# Sheet1.net
KiCad netlist of a schematic drawn in Altium Designer
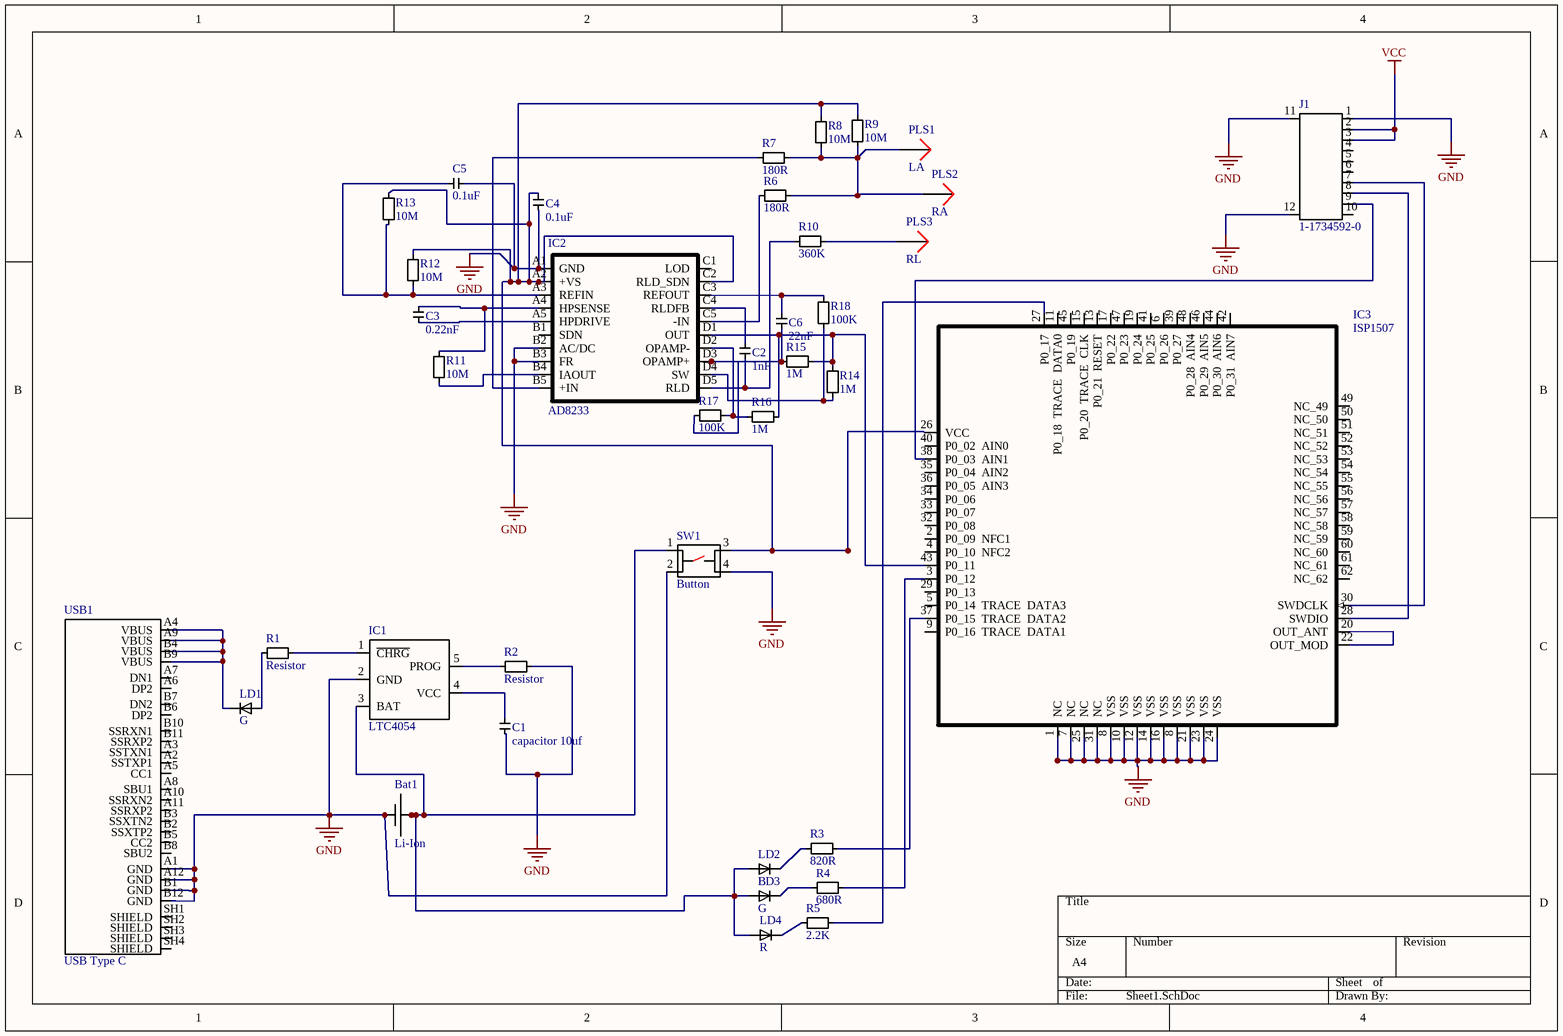
[diagram p0: Sheet1.SchDoc]

(export (version "E")
  (design (tool "Eeschema 10.0.6"))
  (components
    (comp (ref "Bat1") (value "Li-Ion") (footprint "LI-ion") (libsource (lib "Schlib1") (part "Li-Ion")))
    (comp (ref "C2") (value "1nF") (footprint "Capac") (libsource (lib "Schlib1") (part "capacitor 1uf")))
    (comp (ref "C3") (value "0.22nF") (footprint "Capac") (libsource (lib "Schlib1") (part "capacitor 1uf")))
    (comp (ref "C4") (value "0.1uF") (footprint "Capac") (libsource (lib "Schlib1") (part "capacitor 1uf")))
    (comp (ref "C5") (value "0.1uF") (footprint "Capac") (libsource (lib "Schlib1") (part "capacitor 1uf")))
    (comp (ref "C6") (value "22nF") (footprint "Capac") (libsource (lib "Schlib1") (part "capacitor 1uf")))
    (comp (ref "IC1") (value "LTC4054") (footprint "LTC4054") (libsource (lib "Schlib1") (part "LTC4054")))
    (comp (ref "IC2") (value "AD8233") (footprint "AD8233") (libsource (lib "Schlib1") (part "AD8233")))
    (comp (ref "IC3") (value "ISP1507") (footprint "ISP1507") (libsource (lib "Schlib1") (part "ISP1507")))
    (comp (ref "J1")
      (value "1-1734592-0")
      (footprint "1-1734592-0")
      (libsource (lib "Schlib1") (part "1-1734592-0"))
    )
    (comp (ref "LD1") (value "G") (footprint "LED") (libsource (lib "Schlib1") (part "led")))
    (comp (ref "LD2") (value "B") (footprint "LED") (libsource (lib "Schlib1") (part "led")))
    (comp (ref "LD3") (value "G") (footprint "LED") (libsource (lib "Schlib1") (part "led")))
    (comp (ref "LD4") (value "R") (footprint "LED") (libsource (lib "Schlib1") (part "led")))
    (comp (ref "PLS1") (value "LA") (footprint "output") (libsource (lib "Schlib1") (part "Output")))
    (comp (ref "PLS2") (value "RA") (footprint "output") (libsource (lib "Schlib1") (part "Output")))
    (comp (ref "PLS3") (value "RL") (footprint "output") (libsource (lib "Schlib1") (part "Output")))
    (comp (ref "R1")
      (value "Resistor")
      (footprint "Resistor 1")
      (libsource (lib "Schlib1") (part "Resistor"))
    )
    (comp (ref "R2")
      (value "Resistor")
      (footprint "Resistor 1")
      (libsource (lib "Schlib1") (part "Resistor"))
    )
    (comp (ref "R3") (value "820R") (footprint "Resistor 1") (libsource (lib "Schlib1") (part "Resistor")))
    (comp (ref "R4") (value "680R") (footprint "Resistor 1") (libsource (lib "Schlib1") (part "Resistor")))
    (comp (ref "R5") (value "2.2K") (footprint "Resistor 1") (libsource (lib "Schlib1") (part "Resistor")))
    (comp (ref "R6") (value "180R") (footprint "Resistor 1") (libsource (lib "Schlib1") (part "Resistor")))
    (comp (ref "R7") (value "180R") (footprint "Resistor 1") (libsource (lib "Schlib1") (part "Resistor")))
    (comp (ref "R8") (value "10M") (footprint "Resistor 1") (libsource (lib "Schlib1") (part "Resistor")))
    (comp (ref "R9") (value "10M") (footprint "Resistor 1") (libsource (lib "Schlib1") (part "Resistor")))
    (comp (ref "R10") (value "360K") (footprint "Resistor 1") (libsource (lib "Schlib1") (part "Resistor")))
    (comp (ref "R11") (value "10M") (footprint "Resistor 1") (libsource (lib "Schlib1") (part "Resistor")))
    (comp (ref "R12") (value "10M") (footprint "Resistor 1") (libsource (lib "Schlib1") (part "Resistor")))
    (comp (ref "R13") (value "10M") (footprint "Resistor 1") (libsource (lib "Schlib1") (part "Resistor")))
    (comp (ref "R14") (value "1M") (footprint "Resistor 1") (libsource (lib "Schlib1") (part "Resistor")))
    (comp (ref "R15") (value "1M") (footprint "Resistor 1") (libsource (lib "Schlib1") (part "Resistor")))
    (comp (ref "R16") (value "1M") (footprint "Resistor 1") (libsource (lib "Schlib1") (part "Resistor")))
    (comp (ref "R17") (value "100K") (footprint "Resistor 1") (libsource (lib "Schlib1") (part "Resistor")))
    (comp (ref "R18") (value "100K") (footprint "Resistor 1") (libsource (lib "Schlib1") (part "Resistor")))
    (comp (ref "SW1") (value "Button") (footprint "Button") (libsource (lib "Schlib1") (part "Button")))
    (comp (ref "USB1")
      (value "USB Type C")
      (footprint "Type C")
      (libsource (lib "Schlib1") (part "USB Type C"))
    )
    (comp (ref "С1")
      (value "capacitor 10uf")
      (footprint "CAPAC10")
      (libsource (lib "Schlib1") (part "capacitor 10uf"))
    )
  )
  (nets
    (net (code "1") (name "GND") (class "Default")
      (node (ref "Bat1") (pin "1") (pintype "passive"))
      (node (ref "Bat1") (pin "2") (pinfunction "2_2") (pintype "passive"))
      (node (ref "C4") (pin "1") (pinfunction "1_1") (pintype "passive"))
      (node (ref "C5") (pin "2") (pinfunction "2_2") (pintype "passive"))
      (node (ref "IC1") (pin "2") (pinfunction "GND_2") (pintype "power_in"))
      (node (ref "IC2") (pin "A1") (pinfunction "GND_A1") (pintype "passive"))
      (node (ref "IC2") (pin "B2") (pinfunction "AC/DC_B2") (pintype "power_in"))
      (node (ref "IC2") (pin "B3") (pinfunction "FR_B3") (pintype "power_in"))
      (node (ref "IC3") (pin "1") (pinfunction "NC_1") (pintype "power_in"))
      (node (ref "IC3") (pin "10") (pinfunction "VSS_10") (pintype "power_in"))
      (node (ref "IC3") (pin "12") (pinfunction "VSS_12") (pintype "power_in"))
      (node (ref "IC3") (pin "14") (pinfunction "VSS_14") (pintype "power_in"))
      (node (ref "IC3") (pin "16") (pinfunction "VSS_16") (pintype "power_in"))
      (node (ref "IC3") (pin "21") (pinfunction "VSS_21") (pintype "power_in"))
      (node (ref "IC3") (pin "23") (pinfunction "VSS_23") (pintype "power_in"))
      (node (ref "IC3") (pin "24") (pinfunction "VSS_24") (pintype "power_in"))
      (node (ref "IC3") (pin "25") (pinfunction "NC_25") (pintype "power_in"))
      (node (ref "IC3") (pin "31") (pinfunction "NC_31") (pintype "power_in"))
      (node (ref "IC3") (pin "7") (pinfunction "NC_7") (pintype "power_in"))
      (node (ref "IC3") (pin "8") (pinfunction "VSS_8") (pintype "power_in"))
      (node (ref "J1") (pin "1") (pinfunction "1_1") (pintype "passive"))
      (node (ref "J1") (pin "11") (pinfunction "11_11") (pintype "passive"))
      (node (ref "J1") (pin "12") (pinfunction "12_12") (pintype "passive"))
      (node (ref "R2") (pin "2") (pinfunction "2_2") (pintype "passive"))
      (node (ref "SW1") (pin "2") (pinfunction "2_2") (pintype "passive"))
      (node (ref "SW1") (pin "4") (pinfunction "4_4") (pintype "passive"))
      (node (ref "USB1") (pin "A1") (pinfunction "GND_A1") (pintype "passive"))
      (node (ref "USB1") (pin "A12") (pinfunction "GND_A12") (pintype "passive"))
      (node (ref "USB1") (pin "B1") (pinfunction "GND_B1") (pintype "passive"))
      (node (ref "USB1") (pin "B12") (pinfunction "GND_B12") (pintype "passive"))
      (node (ref "С1") (pin "1") (pinfunction "1_1") (pintype "passive"))
    )
    (net (code "2") (name "Net-(IC1-BAT)") (class "Default")
      (node (ref "Bat1") (pin "3") (pinfunction "3_3") (pintype "passive"))
      (node (ref "Bat1") (pin "4") (pinfunction "4_4") (pintype "passive"))
      (node (ref "Bat1") (pin "5") (pinfunction "5_5") (pintype "passive"))
      (node (ref "IC1") (pin "3") (pinfunction "BAT_3") (pintype "passive"))
      (node (ref "LD2") (pin "1") (pinfunction "1_1") (pintype "passive"))
      (node (ref "LD3") (pin "1") (pinfunction "1_1") (pintype "passive"))
      (node (ref "LD4") (pin "1") (pinfunction "1_1") (pintype "passive"))
      (node (ref "SW1") (pin "1") (pinfunction "1_1") (pintype "passive"))
    )
    (net (code "3") (name "Net-(IC1-PROG)") (class "Default")
      (node (ref "IC1") (pin "5") (pinfunction "PROG_5") (pintype "passive"))
      (node (ref "R2") (pin "1") (pinfunction "1_1") (pintype "passive"))
    )
    (net (code "4") (name "Net-(IC1-VCC)") (class "Default")
      (node (ref "IC1") (pin "4") (pinfunction "VCC_4") (pintype "power_in"))
      (node (ref "С1") (pin "2") (pinfunction "2_2") (pintype "passive"))
    )
    (net (code "5") (name "Net-(IC1-~{CHRG})") (class "Default")
      (node (ref "IC1") (pin "1") (pinfunction "~{CHRG}_1") (pintype "passive"))
      (node (ref "R1") (pin "2") (pinfunction "2_2") (pintype "passive"))
    )
    (net (code "6") (name "Net-(IC2-+IN)") (class "Default")
      (node (ref "IC2") (pin "B5") (pinfunction "+IN_B5") (pintype "power_in"))
      (node (ref "R7") (pin "1") (pinfunction "1_1") (pintype "passive"))
    )
    (net (code "7") (name "Net-(IC2-+VS)") (class "Default")
      (node (ref "C4") (pin "2") (pinfunction "2_2") (pintype "passive"))
      (node (ref "IC2") (pin "A2") (pinfunction "+VS_A2") (pintype "passive"))
      (node (ref "IC2") (pin "C2") (pinfunction "RLD_SDN_C2") (pintype "power_in"))
      (node (ref "IC3") (pin "26") (pinfunction "VCC_26") (pintype "power_in"))
      (node (ref "R12") (pin "2") (pinfunction "2_2") (pintype "passive"))
      (node (ref "R13") (pin "2") (pinfunction "2_2") (pintype "passive"))
      (node (ref "R8") (pin "2") (pinfunction "2_2") (pintype "passive"))
      (node (ref "R9") (pin "2") (pinfunction "2_2") (pintype "passive"))
      (node (ref "SW1") (pin "3") (pinfunction "3_3") (pintype "passive"))
    )
    (net (code "8") (name "Net-(IC2--IN)") (class "Default")
      (node (ref "IC2") (pin "C5") (pinfunction "-IN_C5") (pintype "power_in"))
      (node (ref "R6") (pin "1") (pinfunction "1_1") (pintype "passive"))
    )
    (net (code "9") (name "Net-(IC2-HPDRIVE)") (class "Default")
      (node (ref "C3") (pin "1") (pinfunction "1_1") (pintype "passive"))
      (node (ref "IC2") (pin "A5") (pinfunction "HPDRIVE_A5") (pintype "power_in"))
    )
    (net (code "10") (name "Net-(IC2-HPSENSE)") (class "Default")
      (node (ref "C3") (pin "2") (pinfunction "2_2") (pintype "passive"))
      (node (ref "IC2") (pin "A4") (pinfunction "HPSENSE_A4") (pintype "passive"))
      (node (ref "R11") (pin "2") (pinfunction "2_2") (pintype "passive"))
    )
    (net (code "11") (name "Net-(IC2-IAOUT)") (class "Default")
      (node (ref "IC2") (pin "B4") (pinfunction "IAOUT_B4") (pintype "power_in"))
      (node (ref "R11") (pin "1") (pinfunction "1_1") (pintype "passive"))
    )
    (net (code "12") (name "Net-(IC2-OPAMP+)") (class "Default")
      (node (ref "C6") (pin "1") (pinfunction "1_1") (pintype "passive"))
      (node (ref "IC2") (pin "D3") (pinfunction "OPAMP+_D3") (pintype "power_in"))
      (node (ref "R15") (pin "1") (pinfunction "1_1") (pintype "passive"))
      (node (ref "R17") (pin "1") (pinfunction "1_1") (pintype "passive"))
    )
    (net (code "13") (name "Net-(IC2-OPAMP-)") (class "Default")
      (node (ref "IC2") (pin "D2") (pinfunction "OPAMP-_D2") (pintype "power_in"))
      (node (ref "R16") (pin "1") (pinfunction "1_1") (pintype "passive"))
      (node (ref "R17") (pin "2") (pinfunction "2_2") (pintype "passive"))
    )
    (net (code "14") (name "Net-(IC2-OUT)") (class "Default")
      (node (ref "IC2") (pin "D1") (pinfunction "OUT_D1") (pintype "power_in"))
      (node (ref "IC3") (pin "43") (pinfunction "P0_11_43") (pintype "bidirectional"))
      (node (ref "R14") (pin "2") (pinfunction "2_2") (pintype "passive"))
      (node (ref "R15") (pin "2") (pinfunction "2_2") (pintype "passive"))
      (node (ref "R16") (pin "2") (pinfunction "2_2") (pintype "passive"))
    )
    (net (code "15") (name "Net-(IC2-REFIN)") (class "Default")
      (node (ref "C5") (pin "1") (pinfunction "1_1") (pintype "passive"))
      (node (ref "IC2") (pin "A3") (pinfunction "REFIN_A3") (pintype "passive"))
      (node (ref "R12") (pin "1") (pinfunction "1_1") (pintype "passive"))
      (node (ref "R13") (pin "1") (pinfunction "1_1") (pintype "passive"))
    )
    (net (code "16") (name "Net-(IC2-REFOUT)") (class "Default")
      (node (ref "C6") (pin "2") (pinfunction "2_2") (pintype "passive"))
      (node (ref "IC2") (pin "C3") (pinfunction "REFOUT_C3") (pintype "power_in"))
      (node (ref "R18") (pin "2") (pinfunction "2_2") (pintype "passive"))
    )
    (net (code "17") (name "Net-(IC2-RLD)") (class "Default")
      (node (ref "C2") (pin "2") (pinfunction "2_2") (pintype "passive"))
      (node (ref "IC2") (pin "D5") (pinfunction "RLD_D5") (pintype "power_in"))
      (node (ref "R10") (pin "1") (pinfunction "1_1") (pintype "passive"))
    )
    (net (code "18") (name "Net-(IC2-RLDFB)") (class "Default")
      (node (ref "C2") (pin "1") (pinfunction "1_1") (pintype "passive"))
      (node (ref "IC2") (pin "C4") (pinfunction "RLDFB_C4") (pintype "power_in"))
    )
    (net (code "19") (name "Net-(IC2-SW)") (class "Default")
      (node (ref "IC2") (pin "D4") (pinfunction "SW_D4") (pintype "power_in"))
      (node (ref "R14") (pin "1") (pinfunction "1_1") (pintype "passive"))
      (node (ref "R18") (pin "1") (pinfunction "1_1") (pintype "passive"))
    )
    (net (code "20") (name "Net-(IC3-OUT_ANT)") (class "Default")
      (node (ref "IC3") (pin "20") (pinfunction "OUT_ANT_20") (pintype "bidirectional"))
      (node (ref "IC3") (pin "22") (pinfunction "OUT_MOD_22") (pintype "bidirectional"))
    )
    (net (code "21") (name "Net-(IC3-P0_03__AIN1)") (class "Default")
      (node (ref "IC3") (pin "38") (pinfunction "P0_03__AIN1_38") (pintype "bidirectional"))
      (node (ref "J1") (pin "9") (pinfunction "9_9") (pintype "passive"))
    )
    (net (code "22") (name "Net-(IC3-P0_12)") (class "Default")
      (node (ref "IC3") (pin "3") (pinfunction "P0_12_3") (pintype "bidirectional"))
      (node (ref "R4") (pin "2") (pinfunction "2_2") (pintype "passive"))
    )
    (net (code "23") (name "Net-(IC3-P0_15__TRACE__DATA2)") (class "Default")
      (node (ref "IC3") (pin "37") (pinfunction "P0_15__TRACE__DATA2_37") (pintype "bidirectional"))
      (node (ref "R3") (pin "2") (pinfunction "2_2") (pintype "passive"))
    )
    (net (code "24") (name "Net-(IC3-P0_17)") (class "Default")
      (node (ref "IC3") (pin "27") (pinfunction "P0_17_27") (pintype "bidirectional"))
      (node (ref "R5") (pin "2") (pinfunction "2_2") (pintype "passive"))
    )
    (net (code "25") (name "Net-(IC3-SWDCLK)") (class "Default")
      (node (ref "IC3") (pin "30") (pinfunction "SWDCLK_30") (pintype "input"))
      (node (ref "J1") (pin "7") (pinfunction "7_7") (pintype "passive"))
    )
    (net (code "26") (name "Net-(IC3-SWDIO)") (class "Default")
      (node (ref "IC3") (pin "28") (pinfunction "SWDIO_28") (pintype "bidirectional"))
      (node (ref "J1") (pin "8") (pinfunction "8_8") (pintype "passive"))
    )
    (net (code "27") (name "Net-(LD1-Pad1)") (class "Default")
      (node (ref "LD1") (pin "1") (pinfunction "1_1") (pintype "passive"))
      (node (ref "R1") (pin "1") (pinfunction "1_1") (pintype "passive"))
    )
    (net (code "28") (name "Net-(LD1-Pad2)") (class "Default")
      (node (ref "LD1") (pin "2") (pinfunction "2_2") (pintype "passive"))
      (node (ref "USB1") (pin "A4") (pinfunction "VBUS_A4") (pintype "passive"))
      (node (ref "USB1") (pin "A9") (pinfunction "VBUS_A9") (pintype "passive"))
      (node (ref "USB1") (pin "B4") (pinfunction "VBUS_B4") (pintype "passive"))
      (node (ref "USB1") (pin "B9") (pinfunction "VBUS_B9") (pintype "passive"))
    )
    (net (code "29") (name "Net-(LD2-Pad2)") (class "Default")
      (node (ref "LD2") (pin "2") (pinfunction "2_2") (pintype "passive"))
      (node (ref "R3") (pin "1") (pinfunction "1_1") (pintype "passive"))
    )
    (net (code "30") (name "Net-(LD3-Pad2)") (class "Default")
      (node (ref "LD3") (pin "2") (pinfunction "2_2") (pintype "passive"))
      (node (ref "R4") (pin "1") (pinfunction "1_1") (pintype "passive"))
    )
    (net (code "31") (name "Net-(LD4-Pad2)") (class "Default")
      (node (ref "LD4") (pin "2") (pinfunction "2_2") (pintype "passive"))
      (node (ref "R5") (pin "1") (pinfunction "1_1") (pintype "passive"))
    )
    (net (code "32") (name "Net-(PLS1-Pad1)") (class "Default")
      (node (ref "PLS1") (pin "1") (pinfunction "1_1") (pintype "passive"))
      (node (ref "PLS2") (pin "1") (pinfunction "1_1") (pintype "passive"))
      (node (ref "R6") (pin "2") (pinfunction "2_2") (pintype "passive"))
      (node (ref "R7") (pin "2") (pinfunction "2_2") (pintype "passive"))
      (node (ref "R8") (pin "1") (pinfunction "1_1") (pintype "passive"))
      (node (ref "R9") (pin "1") (pinfunction "1_1") (pintype "passive"))
    )
    (net (code "33") (name "Net-(PLS3-Pad1)") (class "Default")
      (node (ref "PLS3") (pin "1") (pinfunction "1_1") (pintype "passive"))
      (node (ref "R10") (pin "2") (pinfunction "2_2") (pintype "passive"))
    )
    (net (code "34") (name "VCC") (class "Default")
      (node (ref "J1") (pin "2") (pinfunction "2_2") (pintype "passive"))
      (node (ref "J1") (pin "3") (pinfunction "3_3") (pintype "passive"))
    )
    (net (code "35") (name "unconnected-(IC2-LOD-PadC1)") (class "Default")
      (node (ref "IC2") (pin "C1") (pinfunction "LOD_C1") (pintype "power_in"))
    )
    (net (code "36") (name "unconnected-(IC2-SDN-PadB1)") (class "Default")
      (node (ref "IC2") (pin "B1") (pinfunction "SDN_B1") (pintype "power_in"))
    )
    (net (code "37") (name "unconnected-(IC3-NC_49-Pad49)") (class "Default")
      (node (ref "IC3") (pin "49") (pinfunction "NC_49_49") (pintype "bidirectional"))
    )
    (net (code "38") (name "unconnected-(IC3-NC_50-Pad50)") (class "Default")
      (node (ref "IC3") (pin "50") (pinfunction "NC_50_50") (pintype "bidirectional"))
    )
    (net (code "39") (name "unconnected-(IC3-NC_51-Pad51)") (class "Default")
      (node (ref "IC3") (pin "51") (pinfunction "NC_51_51") (pintype "bidirectional"))
    )
    (net (code "40") (name "unconnected-(IC3-NC_52-Pad52)") (class "Default")
      (node (ref "IC3") (pin "52") (pinfunction "NC_52_52") (pintype "bidirectional"))
    )
    (net (code "41") (name "unconnected-(IC3-NC_53-Pad53)") (class "Default")
      (node (ref "IC3") (pin "53") (pinfunction "NC_53_53") (pintype "bidirectional"))
    )
    (net (code "42") (name "unconnected-(IC3-NC_54-Pad54)") (class "Default")
      (node (ref "IC3") (pin "54") (pinfunction "NC_54_54") (pintype "bidirectional"))
    )
    (net (code "43") (name "unconnected-(IC3-NC_55-Pad55)") (class "Default")
      (node (ref "IC3") (pin "55") (pinfunction "NC_55_55") (pintype "bidirectional"))
    )
    (net (code "44") (name "unconnected-(IC3-NC_56-Pad56)") (class "Default")
      (node (ref "IC3") (pin "56") (pinfunction "NC_56_56") (pintype "bidirectional"))
    )
    (net (code "45") (name "unconnected-(IC3-NC_57-Pad57)") (class "Default")
      (node (ref "IC3") (pin "57") (pinfunction "NC_57_57") (pintype "bidirectional"))
    )
    (net (code "46") (name "unconnected-(IC3-NC_58-Pad58)") (class "Default")
      (node (ref "IC3") (pin "58") (pinfunction "NC_58_58") (pintype "bidirectional"))
    )
    (net (code "47") (name "unconnected-(IC3-NC_59-Pad59)") (class "Default")
      (node (ref "IC3") (pin "59") (pinfunction "NC_59_59") (pintype "bidirectional"))
    )
    (net (code "48") (name "unconnected-(IC3-NC_60-Pad60)") (class "Default")
      (node (ref "IC3") (pin "60") (pinfunction "NC_60_60") (pintype "bidirectional"))
    )
    (net (code "49") (name "unconnected-(IC3-NC_61-Pad61)") (class "Default")
      (node (ref "IC3") (pin "61") (pinfunction "NC_61_61") (pintype "bidirectional"))
    )
    (net (code "50") (name "unconnected-(IC3-NC_62-Pad62)") (class "Default")
      (node (ref "IC3") (pin "62") (pinfunction "NC_62_62") (pintype "bidirectional"))
    )
    (net (code "51") (name "unconnected-(IC3-P0_02__AIN0-Pad40)") (class "Default")
      (node (ref "IC3") (pin "40") (pinfunction "P0_02__AIN0_40") (pintype "bidirectional"))
    )
    (net (code "52") (name "unconnected-(IC3-P0_04__AIN2-Pad35)") (class "Default")
      (node (ref "IC3") (pin "35") (pinfunction "P0_04__AIN2_35") (pintype "bidirectional"))
    )
    (net (code "53") (name "unconnected-(IC3-P0_05__AIN3-Pad36)") (class "Default")
      (node (ref "IC3") (pin "36") (pinfunction "P0_05__AIN3_36") (pintype "bidirectional"))
    )
    (net (code "54") (name "unconnected-(IC3-P0_06-Pad34)") (class "Default")
      (node (ref "IC3") (pin "34") (pinfunction "P0_06_34") (pintype "bidirectional"))
    )
    (net (code "55") (name "unconnected-(IC3-P0_07-Pad33)") (class "Default")
      (node (ref "IC3") (pin "33") (pinfunction "P0_07_33") (pintype "bidirectional"))
    )
    (net (code "56") (name "unconnected-(IC3-P0_08-Pad32)") (class "Default")
      (node (ref "IC3") (pin "32") (pinfunction "P0_08_32") (pintype "bidirectional"))
    )
    (net (code "57") (name "unconnected-(IC3-P0_09__NFC1-Pad2)") (class "Default")
      (node (ref "IC3") (pin "2") (pinfunction "P0_09__NFC1_2") (pintype "bidirectional"))
    )
    (net (code "58") (name "unconnected-(IC3-P0_10__NFC2-Pad4)") (class "Default")
      (node (ref "IC3") (pin "4") (pinfunction "P0_10__NFC2_4") (pintype "bidirectional"))
    )
    (net (code "59") (name "unconnected-(IC3-P0_13-Pad29)") (class "Default")
      (node (ref "IC3") (pin "29") (pinfunction "P0_13_29") (pintype "bidirectional"))
    )
    (net (code "60") (name "unconnected-(IC3-P0_14__TRACE__DATA3-Pad5)") (class "Default")
      (node (ref "IC3") (pin "5") (pinfunction "P0_14__TRACE__DATA3_5") (pintype "bidirectional"))
    )
    (net (code "61") (name "unconnected-(IC3-P0_16__TRACE__DATA1-Pad9)") (class "Default")
      (node (ref "IC3") (pin "9") (pinfunction "P0_16__TRACE__DATA1_9") (pintype "bidirectional"))
    )
    (net (code "62") (name "unconnected-(IC3-P0_18__TRACE__DATA0-Pad11)") (class "Default")
      (node (ref "IC3") (pin "11") (pinfunction "P0_18__TRACE__DATA0_11") (pintype "bidirectional"))
    )
    (net (code "63") (name "unconnected-(IC3-P0_19-Pad45)") (class "Default")
      (node (ref "IC3") (pin "45") (pinfunction "P0_19_45") (pintype "bidirectional"))
    )
    (net (code "64") (name "unconnected-(IC3-P0_20__TRACE__CLK-Pad15)") (class "Default")
      (node (ref "IC3") (pin "15") (pinfunction "P0_20__TRACE__CLK_15") (pintype "bidirectional"))
    )
    (net (code "65") (name "unconnected-(IC3-P0_21__RESET-Pad13)") (class "Default")
      (node (ref "IC3") (pin "13") (pinfunction "P0_21__RESET_13") (pintype "bidirectional"))
    )
    (net (code "66") (name "unconnected-(IC3-P0_22-Pad17)") (class "Default")
      (node (ref "IC3") (pin "17") (pinfunction "P0_22_17") (pintype "bidirectional"))
    )
    (net (code "67") (name "unconnected-(IC3-P0_23-Pad47)") (class "Default")
      (node (ref "IC3") (pin "47") (pinfunction "P0_23_47") (pintype "bidirectional"))
    )
    (net (code "68") (name "unconnected-(IC3-P0_24-Pad19)") (class "Default")
      (node (ref "IC3") (pin "19") (pinfunction "P0_24_19") (pintype "bidirectional"))
    )
    (net (code "69") (name "unconnected-(IC3-P0_25-Pad41)") (class "Default")
      (node (ref "IC3") (pin "41") (pinfunction "P0_25_41") (pintype "bidirectional"))
    )
    (net (code "70") (name "unconnected-(IC3-P0_26-Pad6)") (class "Default")
      (node (ref "IC3") (pin "6") (pinfunction "P0_26_6") (pintype "bidirectional"))
    )
    (net (code "71") (name "unconnected-(IC3-P0_27-Pad39)") (class "Default")
      (node (ref "IC3") (pin "39") (pinfunction "P0_27_39") (pintype "bidirectional"))
    )
    (net (code "72") (name "unconnected-(IC3-P0_28__AIN4-Pad48)") (class "Default")
      (node (ref "IC3") (pin "48") (pinfunction "P0_28__AIN4_48") (pintype "bidirectional"))
    )
    (net (code "73") (name "unconnected-(IC3-P0_29__AIN5-Pad46)") (class "Default")
      (node (ref "IC3") (pin "46") (pinfunction "P0_29__AIN5_46") (pintype "bidirectional"))
    )
    (net (code "74") (name "unconnected-(IC3-P0_30__AIN6-Pad44)") (class "Default")
      (node (ref "IC3") (pin "44") (pinfunction "P0_30__AIN6_44") (pintype "bidirectional"))
    )
    (net (code "75") (name "unconnected-(IC3-P0_31__AIN7-Pad42)") (class "Default")
      (node (ref "IC3") (pin "42") (pinfunction "P0_31__AIN7_42") (pintype "bidirectional"))
    )
    (net (code "76") (name "unconnected-(J1-Pad4)") (class "Default")
      (node (ref "J1") (pin "4") (pinfunction "4_4") (pintype "passive"))
    )
    (net (code "77") (name "unconnected-(J1-Pad5)") (class "Default")
      (node (ref "J1") (pin "5") (pinfunction "5_5") (pintype "passive"))
    )
    (net (code "78") (name "unconnected-(J1-Pad6)") (class "Default")
      (node (ref "J1") (pin "6") (pinfunction "6_6") (pintype "passive"))
    )
    (net (code "79") (name "unconnected-(J1-Pad10)") (class "Default")
      (node (ref "J1") (pin "10") (pinfunction "10_10") (pintype "passive"))
    )
    (net (code "80") (name "unconnected-(USB1-CC1-PadA5)") (class "Default")
      (node (ref "USB1") (pin "A5") (pinfunction "CC1_A5") (pintype "passive"))
    )
    (net (code "81") (name "unconnected-(USB1-CC2-PadB5)") (class "Default")
      (node (ref "USB1") (pin "B5") (pinfunction "CC2_B5") (pintype "passive"))
    )
    (net (code "82") (name "unconnected-(USB1-DN1-PadA7)") (class "Default")
      (node (ref "USB1") (pin "A7") (pinfunction "DN1_A7") (pintype "passive"))
    )
    (net (code "83") (name "unconnected-(USB1-DN2-PadB7)") (class "Default")
      (node (ref "USB1") (pin "B7") (pinfunction "DN2_B7") (pintype "passive"))
    )
    (net (code "84") (name "unconnected-(USB1-DP2-PadA6)") (class "Default")
      (node (ref "USB1") (pin "A6") (pinfunction "DP2_A6") (pintype "passive"))
    )
    (net (code "85") (name "unconnected-(USB1-DP2-PadB6)") (class "Default")
      (node (ref "USB1") (pin "B6") (pinfunction "DP2_B6") (pintype "passive"))
    )
    (net (code "86") (name "unconnected-(USB1-SBU1-PadA8)") (class "Default")
      (node (ref "USB1") (pin "A8") (pinfunction "SBU1_A8") (pintype "passive"))
    )
    (net (code "87") (name "unconnected-(USB1-SBU2-PadB8)") (class "Default")
      (node (ref "USB1") (pin "B8") (pinfunction "SBU2_B8") (pintype "passive"))
    )
    (net (code "88") (name "unconnected-(USB1-SHIELD-PadSH1)") (class "Default")
      (node (ref "USB1") (pin "SH1") (pinfunction "SHIELD_SH1") (pintype "passive"))
    )
    (net (code "89") (name "unconnected-(USB1-SHIELD-PadSH2)") (class "Default")
      (node (ref "USB1") (pin "SH2") (pinfunction "SHIELD_SH2") (pintype "passive"))
    )
    (net (code "90") (name "unconnected-(USB1-SHIELD-PadSH3)") (class "Default")
      (node (ref "USB1") (pin "SH3") (pinfunction "SHIELD_SH3") (pintype "passive"))
    )
    (net (code "91") (name "unconnected-(USB1-SHIELD-PadSH4)") (class "Default")
      (node (ref "USB1") (pin "SH4") (pinfunction "SHIELD_SH4") (pintype "passive"))
    )
    (net (code "92") (name "unconnected-(USB1-SSRXN1-PadB10)") (class "Default")
      (node (ref "USB1") (pin "B10") (pinfunction "SSRXN1_B10") (pintype "passive"))
    )
    (net (code "93") (name "unconnected-(USB1-SSRXN2-PadA10)") (class "Default")
      (node (ref "USB1") (pin "A10") (pinfunction "SSRXN2_A10") (pintype "passive"))
    )
    (net (code "94") (name "unconnected-(USB1-SSRXP2-PadA11)") (class "Default")
      (node (ref "USB1") (pin "A11") (pinfunction "SSRXP2_A11") (pintype "passive"))
    )
    (net (code "95") (name "unconnected-(USB1-SSRXP2-PadB11)") (class "Default")
      (node (ref "USB1") (pin "B11") (pinfunction "SSRXP2_B11") (pintype "passive"))
    )
    (net (code "96") (name "unconnected-(USB1-SSTXN1-PadA3)") (class "Default")
      (node (ref "USB1") (pin "A3") (pinfunction "SSTXN1_A3") (pintype "passive"))
    )
    (net (code "97") (name "unconnected-(USB1-SSTXP1-PadA2)") (class "Default")
      (node (ref "USB1") (pin "A2") (pinfunction "SSTXP1_A2") (pintype "passive"))
    )
    (net (code "98") (name "unconnected-(USB1-SSXTN2-PadB3)") (class "Default")
      (node (ref "USB1") (pin "B3") (pinfunction "SSXTN2_B3") (pintype "passive"))
    )
    (net (code "99") (name "unconnected-(USB1-SSXTP2-PadB2)") (class "Default")
      (node (ref "USB1") (pin "B2") (pinfunction "SSXTP2_B2") (pintype "passive"))
    )
  )
)
